# ControlBoard_p1.net
KiCad netlist of a schematic drawn in Altium Designer
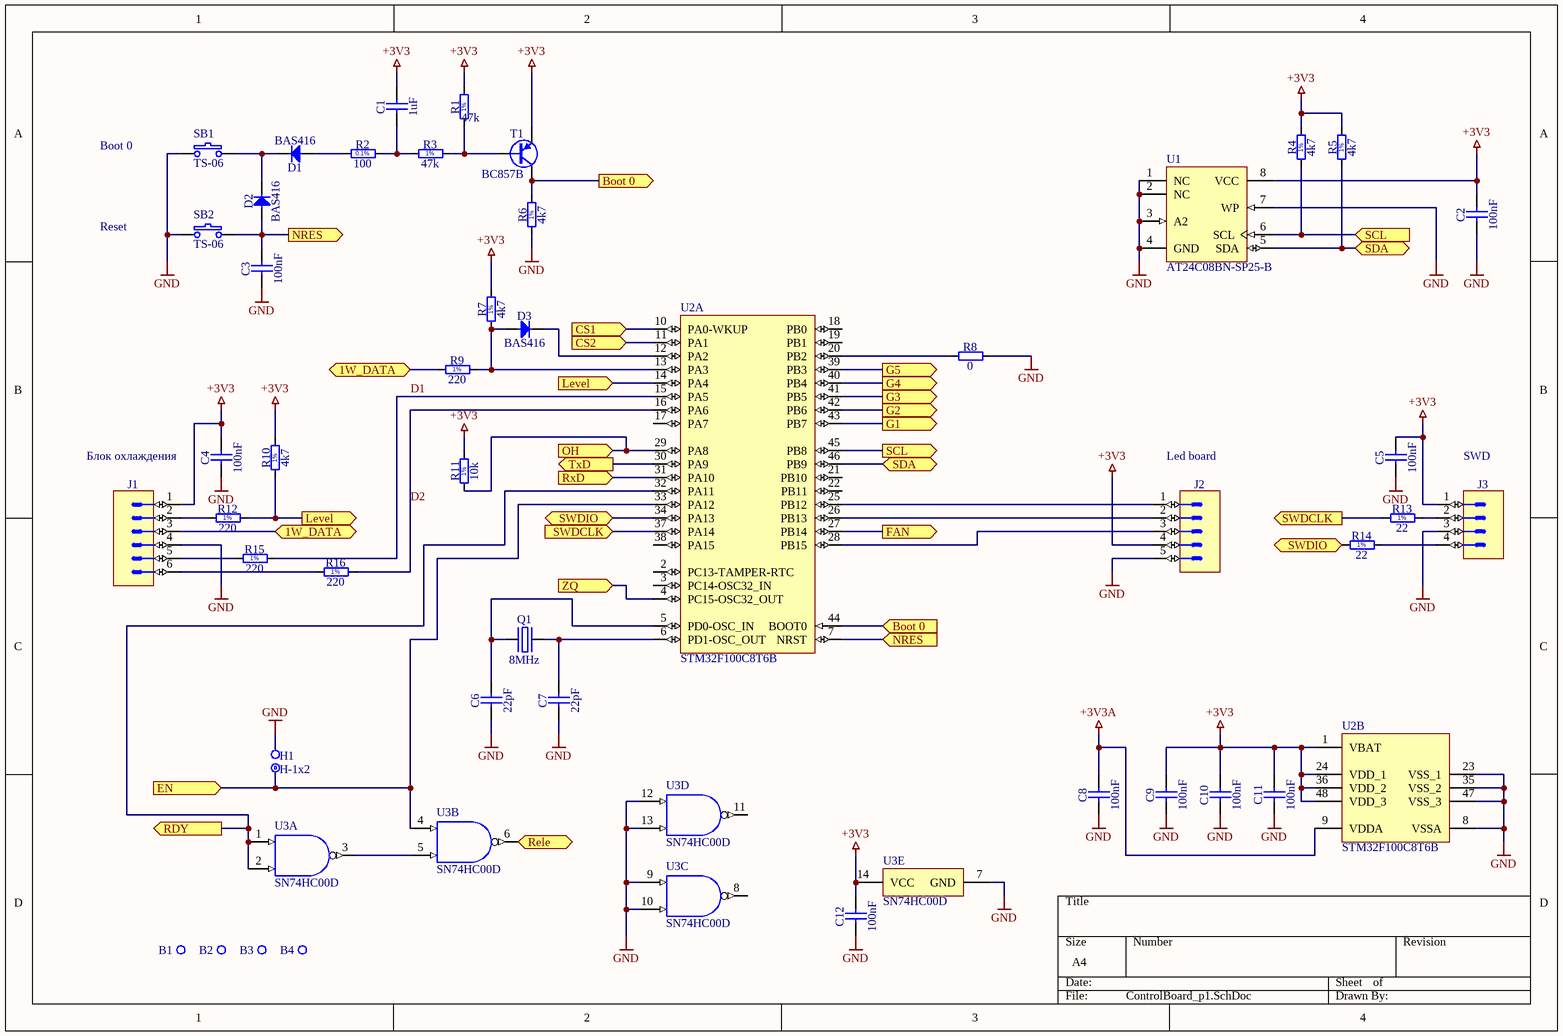
[diagram p0: ControlBoard_p1.SchDoc]

(export (version "E")
  (design (tool "Eeschema 10.0.6"))
  (components
    (comp (ref "B1")
      (value "Plated Hole")
      (footprint "MTG350_650")
      (description "Single Terminal Socket")
      (fields (field (name "PART NUMBER") "PLATED_HOLE3.5_PAD6.5") (field (name "AUTHOR") "CERN DEM JLC"))
      (libsource (lib "Eletro-mechanical") (part "Single Terminal Socket"))
    )
    (comp (ref "B2")
      (value "Plated Hole")
      (footprint "MTG350_650")
      (description "Single Terminal Socket")
      (fields (field (name "PART NUMBER") "PLATED_HOLE3.5_PAD6.5") (field (name "AUTHOR") "CERN DEM JLC"))
      (libsource (lib "Eletro-mechanical") (part "Single Terminal Socket"))
    )
    (comp (ref "B3")
      (value "Plated Hole")
      (footprint "MTG350_650")
      (description "Single Terminal Socket")
      (fields (field (name "PART NUMBER") "PLATED_HOLE3.5_PAD6.5") (field (name "AUTHOR") "CERN DEM JLC"))
      (libsource (lib "Eletro-mechanical") (part "Single Terminal Socket"))
    )
    (comp (ref "B4")
      (value "Plated Hole")
      (footprint "MTG350_650")
      (description "Single Terminal Socket")
      (fields (field (name "PART NUMBER") "PLATED_HOLE3.5_PAD6.5") (field (name "AUTHOR") "CERN DEM JLC"))
      (libsource (lib "Eletro-mechanical") (part "Single Terminal Socket"))
    )
    (comp (ref "C1")
      (value "1uF")
      (footprint "CAPC2012X140N")
      (description "Non-polarised capacitor")
      (fields
        (field (name "PART NUMBER") "CC0805_1UF_35V_20%_X7R")
        (field (name "VOLTAGE") "35V")
        (field (name "AUTHOR") "CERN DEM JLC")
      )
      (libsource (lib "Capacitors") (part "Capacitor - non polarized"))
    )
    (comp (ref "C2")
      (value "100nF")
      (footprint "CAPC2012X135N")
      (description "Non-polarised capacitor")
      (fields
        (field (name "PART NUMBER") "CC0805_100NF_50V_10%_X7R")
        (field (name "VOLTAGE") "50V")
        (field (name "AUTHOR") "CERN DEM JLC")
      )
      (libsource (lib "Capacitors") (part "Capacitor - non polarized"))
    )
    (comp (ref "C3")
      (value "100nF")
      (footprint "CAPC2012X135N")
      (description "Non-polarised capacitor")
      (fields
        (field (name "PART NUMBER") "CC0805_100NF_50V_10%_X7R")
        (field (name "VOLTAGE") "50V")
        (field (name "AUTHOR") "CERN DEM JLC")
      )
      (libsource (lib "Capacitors") (part "Capacitor - non polarized"))
    )
    (comp (ref "C4")
      (value "100nF")
      (footprint "CAPC2012X135N")
      (description "Non-polarised capacitor")
      (fields
        (field (name "PART NUMBER") "CC0805_100NF_50V_10%_X7R")
        (field (name "VOLTAGE") "50V")
        (field (name "AUTHOR") "CERN DEM JLC")
      )
      (libsource (lib "Capacitors") (part "Capacitor - non polarized"))
    )
    (comp (ref "C5")
      (value "100nF")
      (footprint "CAPC2012X135N")
      (description "Non-polarised capacitor")
      (fields
        (field (name "PART NUMBER") "CC0805_100NF_50V_10%_X7R")
        (field (name "VOLTAGE") "50V")
        (field (name "AUTHOR") "CERN DEM JLC")
      )
      (libsource (lib "Capacitors") (part "Capacitor - non polarized"))
    )
    (comp (ref "C6")
      (value "22pF")
      (footprint "CAPC2012X135N")
      (description "Non-polarised capacitor")
      (fields
        (field (name "PART NUMBER") "CC0805_22PF_50V_5%_NP0")
        (field (name "VOLTAGE") "50V")
        (field (name "AUTHOR") "CERN DEM JLC")
      )
      (libsource (lib "Capacitors") (part "Capacitor - non polarized"))
    )
    (comp (ref "C7")
      (value "22pF")
      (footprint "CAPC2012X135N")
      (description "Non-polarised capacitor")
      (fields
        (field (name "PART NUMBER") "CC0805_22PF_50V_5%_NP0")
        (field (name "VOLTAGE") "50V")
        (field (name "AUTHOR") "CERN DEM JLC")
      )
      (libsource (lib "Capacitors") (part "Capacitor - non polarized"))
    )
    (comp (ref "C8")
      (value "100nF")
      (footprint "CAPC2012X135N")
      (description "Non-polarised capacitor")
      (fields
        (field (name "PART NUMBER") "CC0805_100NF_50V_10%_X7R")
        (field (name "VOLTAGE") "50V")
        (field (name "AUTHOR") "CERN DEM JLC")
      )
      (libsource (lib "Capacitors") (part "Capacitor - non polarized"))
    )
    (comp (ref "C9")
      (value "100nF")
      (footprint "CAPC2012X135N")
      (description "Non-polarised capacitor")
      (fields
        (field (name "PART NUMBER") "CC0805_100NF_50V_10%_X7R")
        (field (name "VOLTAGE") "50V")
        (field (name "AUTHOR") "CERN DEM JLC")
      )
      (libsource (lib "Capacitors") (part "Capacitor - non polarized"))
    )
    (comp (ref "C10")
      (value "100nF")
      (footprint "CAPC2012X135N")
      (description "Non-polarised capacitor")
      (fields
        (field (name "PART NUMBER") "CC0805_100NF_50V_10%_X7R")
        (field (name "VOLTAGE") "50V")
        (field (name "AUTHOR") "CERN DEM JLC")
      )
      (libsource (lib "Capacitors") (part "Capacitor - non polarized"))
    )
    (comp (ref "C11")
      (value "100nF")
      (footprint "CAPC2012X135N")
      (description "Non-polarised capacitor")
      (fields
        (field (name "PART NUMBER") "CC0805_100NF_50V_10%_X7R")
        (field (name "VOLTAGE") "50V")
        (field (name "AUTHOR") "CERN DEM JLC")
      )
      (libsource (lib "Capacitors") (part "Capacitor - non polarized"))
    )
    (comp (ref "C12")
      (value "100nF")
      (footprint "CAPC2012X135N")
      (description "Non-polarised capacitor")
      (fields
        (field (name "PART NUMBER") "CC0805_100NF_50V_10%_X7R")
        (field (name "VOLTAGE") "50V")
        (field (name "AUTHOR") "CERN DEM JLC")
      )
      (libsource (lib "Capacitors") (part "Capacitor - non polarized"))
    )
    (comp (ref "D1")
      (value "BAS416")
      (footprint "SOD2512X110N")
      (description "Diode")
      (fields
        (field (name "VOLTAGE") "75V")
        (field (name "POWER") "200mA")
        (field (name "AUTHOR") "CERN DEM JLC")
      )
      (libsource (lib "ICs And Semiconductors") (part "Diode"))
    )
    (comp (ref "D2")
      (value "BAS416")
      (footprint "SOD2512X110N")
      (description "Diode")
      (fields
        (field (name "VOLTAGE") "75V")
        (field (name "POWER") "200mA")
        (field (name "AUTHOR") "CERN DEM JLC")
      )
      (libsource (lib "ICs And Semiconductors") (part "Diode"))
    )
    (comp (ref "D3")
      (value "BAS416")
      (footprint "SOD2512X110N")
      (description "Diode")
      (fields
        (field (name "VOLTAGE") "75V")
        (field (name "POWER") "200mA")
        (field (name "AUTHOR") "CERN DEM JLC")
      )
      (libsource (lib "ICs And Semiconductors") (part "Diode"))
    )
    (comp (ref "H1") (value "H-1x2") (footprint "J1x2") (libsource (lib "Connektor") (part "H-1x2")))
    (comp (ref "J1")
      (value "KK®")
      (footprint "MOLEX_22-27-2061")
      (description "Connector 6 Male")
      (fields
        (field (name "PART NUMBER") "MOLEX_22-27-2061")
        (field (name "MANUFACTURER") "MOLEX")
        (field (name "AUTHOR") "CERN DEM JMW")
      )
      (libsource (lib "Connectors") (part "Connector 6 Male"))
    )
    (comp (ref "J2")
      (value "KK®")
      (footprint "MOLEX_22-27-2051")
      (description "Connector 5 Male")
      (fields
        (field (name "PART NUMBER") "MOLEX_22-27-2051")
        (field (name "MANUFACTURER") "MOLEX")
        (field (name "AUTHOR") "CERN DEM JLC")
      )
      (libsource (lib "Connectors") (part "Connector 5 Male"))
    )
    (comp (ref "J3")
      (value "KK®")
      (footprint "MOLEX_22-27-2041")
      (description "Connector 4 Male")
      (fields
        (field (name "PART NUMBER") "MOLEX_22-27-2041")
        (field (name "MANUFACTURER") "MOLEX")
        (field (name "AUTHOR") "CERN DEM JLC")
      )
      (libsource (lib "Connectors") (part "Connector 4 Male"))
    )
    (comp (ref "Q1")
      (value "8MHz")
      (footprint "XTAL_HC-49/U-S")
      (description "Quartz Crystal")
      (fields
        (field (name "PART NUMBER") "XTAL_5MHZ_CITIZEN_HC49US5.000MABJ-UB")
        (field (name "MANUFACTURER") "CITIZEN FINETECH MIYOTA CO")
        (field (name "AUTHOR") "CERN DEM JLC")
      )
      (libsource (lib "ICs And Semiconductors") (part "Quartz Crystal"))
    )
    (comp (ref "R1")
      (value "47k")
      (footprint "RESC2012X60N")
      (description "Resistor - 1%")
      (fields
        (field (name "PART NUMBER") "R0805_47K_1%_0.125W_100PPM")
        (field (name "POWER") "0.125W")
        (field (name "AUTHOR") "CERN DEM JLC")
      )
      (libsource (lib "Resistors") (part "Resistor - 1%"))
    )
    (comp (ref "R2")
      (value "100")
      (footprint "RESC2012X60N")
      (description "Resistor - 0.1%")
      (fields
        (field (name "PART NUMBER") "R0805_100R_0.1%_0.1W_10PPM")
        (field (name "POWER") "0.1W")
        (field (name "AUTHOR") "CERN DEM JLC")
      )
      (libsource (lib "Resistors") (part "Resistor - 0.1%"))
    )
    (comp (ref "R3")
      (value "47k")
      (footprint "RESC2012X60N")
      (description "Resistor - 1%")
      (fields
        (field (name "PART NUMBER") "R0805_47K_1%_0.125W_100PPM")
        (field (name "POWER") "0.125W")
        (field (name "AUTHOR") "CERN DEM JLC")
      )
      (libsource (lib "Resistors") (part "Resistor - 1%"))
    )
    (comp (ref "R4")
      (value "4k7")
      (footprint "RESC2012X60N")
      (description "Resistor - 1%")
      (fields
        (field (name "PART NUMBER") "R0805_4K7_1%_0.125W_100PPM")
        (field (name "POWER") "0.125W")
        (field (name "AUTHOR") "CERN DEM JLC")
      )
      (libsource (lib "Resistors") (part "Resistor - 1%"))
    )
    (comp (ref "R5")
      (value "4k7")
      (footprint "RESC2012X60N")
      (description "Resistor - 1%")
      (fields
        (field (name "PART NUMBER") "R0805_4K7_1%_0.125W_100PPM")
        (field (name "POWER") "0.125W")
        (field (name "AUTHOR") "CERN DEM JLC")
      )
      (libsource (lib "Resistors") (part "Resistor - 1%"))
    )
    (comp (ref "R6")
      (value "4k7")
      (footprint "RESC2012X60N")
      (description "Resistor - 1%")
      (fields
        (field (name "PART NUMBER") "R0805_4K7_1%_0.125W_100PPM")
        (field (name "POWER") "0.125W")
        (field (name "AUTHOR") "CERN DEM JLC")
      )
      (libsource (lib "Resistors") (part "Resistor - 1%"))
    )
    (comp (ref "R7")
      (value "4k7")
      (footprint "RESC2012X60N")
      (description "Resistor - 1%")
      (fields
        (field (name "PART NUMBER") "R0805_4K7_1%_0.125W_100PPM")
        (field (name "POWER") "0.125W")
        (field (name "AUTHOR") "CERN DEM JLC")
      )
      (libsource (lib "Resistors") (part "Resistor - 1%"))
    )
    (comp (ref "R8")
      (value "0")
      (footprint "RESC2012X60N")
      (description "Resistor")
      (fields
        (field (name "PART NUMBER") "R0805_0R_JUMPER")
        (field (name "MANUFACTURER") "GENERIC")
        (field (name "AUTHOR") "CERN DEM JLC")
      )
      (libsource (lib "Resistors") (part "Resistor"))
    )
    (comp (ref "R9")
      (value "220")
      (footprint "RESC2012X60N")
      (description "Resistor - 1%")
      (fields
        (field (name "PART NUMBER") "R0805_220R_1%_0.125W_100PPM")
        (field (name "POWER") "0.125W")
        (field (name "AUTHOR") "CERN DEM JLC")
      )
      (libsource (lib "Resistors") (part "Resistor - 1%"))
    )
    (comp (ref "R10")
      (value "4k7")
      (footprint "RESC2012X60N")
      (description "Resistor - 1%")
      (fields
        (field (name "PART NUMBER") "R0805_4K7_1%_0.125W_100PPM")
        (field (name "POWER") "0.125W")
        (field (name "AUTHOR") "CERN DEM JLC")
      )
      (libsource (lib "Resistors") (part "Resistor - 1%"))
    )
    (comp (ref "R11")
      (value "10k")
      (footprint "RESC2012X60N")
      (description "Resistor - 1%")
      (fields
        (field (name "PART NUMBER") "R0805_10K_1%_0.125W_100PPM")
        (field (name "POWER") "0.125W")
        (field (name "AUTHOR") "CERN DEM JLC")
      )
      (libsource (lib "Resistors") (part "Resistor - 1%"))
    )
    (comp (ref "R12")
      (value "220")
      (footprint "RESC2012X60N")
      (description "Resistor - 1%")
      (fields
        (field (name "PART NUMBER") "R0805_220R_1%_0.125W_100PPM")
        (field (name "POWER") "0.125W")
        (field (name "AUTHOR") "CERN DEM JLC")
      )
      (libsource (lib "Resistors") (part "Resistor - 1%"))
    )
    (comp (ref "R13")
      (value "22")
      (footprint "RESC2012X60N")
      (description "Resistor - 1%")
      (fields
        (field (name "PART NUMBER") "R0805_22R_1%_0.125W_100PPM")
        (field (name "POWER") "0.125W")
        (field (name "AUTHOR") "CERN DEM JLC")
      )
      (libsource (lib "Resistors") (part "Resistor - 1%"))
    )
    (comp (ref "R14")
      (value "22")
      (footprint "RESC2012X60N")
      (description "Resistor - 1%")
      (fields
        (field (name "PART NUMBER") "R0805_22R_1%_0.125W_100PPM")
        (field (name "POWER") "0.125W")
        (field (name "AUTHOR") "CERN DEM JLC")
      )
      (libsource (lib "Resistors") (part "Resistor - 1%"))
    )
    (comp (ref "R15")
      (value "220")
      (footprint "RESC2012X60N")
      (description "Resistor - 1%")
      (fields
        (field (name "PART NUMBER") "R0805_220R_1%_0.125W_100PPM")
        (field (name "POWER") "0.125W")
        (field (name "AUTHOR") "CERN DEM JLC")
      )
      (libsource (lib "Resistors") (part "Resistor - 1%"))
    )
    (comp (ref "R16")
      (value "220")
      (footprint "RESC2012X60N")
      (description "Resistor - 1%")
      (fields
        (field (name "PART NUMBER") "R0805_220R_1%_0.125W_100PPM")
        (field (name "POWER") "0.125W")
        (field (name "AUTHOR") "CERN DEM JLC")
      )
      (libsource (lib "Resistors") (part "Resistor - 1%"))
    )
    (comp (ref "SB1") (value "TS-06") (footprint "TS-06") (libsource (lib "Devise") (part "Buton TS-06")))
    (comp (ref "SB2") (value "TS-06") (footprint "TS-06") (libsource (lib "Devise") (part "Buton TS-06")))
    (comp (ref "T1")
      (value "BC857B")
      (footprint "SOT95P230X110-3N")
      (description "PNP Transistor")
      (fields (field (name "MANUFACTURER") "NXP SEMICONDUCTORS") (field (name "AUTHOR") "CERN DEM JLC"))
      (libsource (lib "ICs And Semiconductors") (part "PNP B1 E2 C3"))
    )
    (comp (ref "U1")
      (value "AT24C08BN-SP25-B")
      (footprint "8S1_N")
      (description "8Kbit (1024 x 8), 2-wire Bus Automotive Serial EEPROM with Write Protect, 2.5V, 8-Pin SOIC, Bulk")
      (libsource (lib "Atmel Serial EEPROM") (part "AT24C08BN-SP25-B"))
    )
    (comp (ref "U2")
      (value "STM32F100C8T6B")
      (footprint "STM-LQFP48_N")
      (libsource (lib "STMicroelectronics STM32 F1") (part "STM32F100C8T6B"))
    )
    (comp (ref "U3")
      (value "SN74HC00D")
      (footprint "D0014A_N")
      (description "Quad 2-Input Positive-NAND Gates, D0014A, TUBE")
      (fields
        (field (name "GENERIC PART NUMBER") "SN74HC00")
        (field (name "MANUFACTURER") "Texas Instruments")
      )
      (libsource (lib "TI_Logic_Gate") (part "SN74HC00D"))
    )
  )
  (nets
    (net (code "1") (name "+3V3") (class "Default")
      (node (ref "C1") (pin "2") (pinfunction "2_2") (pintype "passive"))
      (node (ref "C10") (pin "2") (pinfunction "2_2") (pintype "passive"))
      (node (ref "C11") (pin "2") (pinfunction "2_2") (pintype "passive"))
      (node (ref "C12") (pin "2") (pinfunction "2_2") (pintype "passive"))
      (node (ref "C2") (pin "2") (pinfunction "2_2") (pintype "passive"))
      (node (ref "C4") (pin "2") (pinfunction "2_2") (pintype "passive"))
      (node (ref "C5") (pin "2") (pinfunction "2_2") (pintype "passive"))
      (node (ref "C9") (pin "2") (pinfunction "2_2") (pintype "passive"))
      (node (ref "J1") (pin "1") (pinfunction "1_1") (pintype "bidirectional"))
      (node (ref "J2") (pin "4") (pinfunction "4_4") (pintype "bidirectional"))
      (node (ref "J3") (pin "1") (pinfunction "1_1") (pintype "bidirectional"))
      (node (ref "R1") (pin "2") (pinfunction "2_2") (pintype "passive"))
      (node (ref "R10") (pin "2") (pinfunction "2_2") (pintype "passive"))
      (node (ref "R11") (pin "2") (pinfunction "2_2") (pintype "passive"))
      (node (ref "R4") (pin "2") (pinfunction "2_2") (pintype "passive"))
      (node (ref "R5") (pin "2") (pinfunction "2_2") (pintype "passive"))
      (node (ref "R7") (pin "2") (pinfunction "2_2") (pintype "passive"))
      (node (ref "T1") (pin "2") (pinfunction "E_2") (pintype "passive"))
      (node (ref "U1") (pin "8") (pinfunction "VCC_8") (pintype "power_in"))
      (node (ref "U2") (pin "1") (pinfunction "VBAT_1") (pintype "power_in"))
      (node (ref "U2") (pin "24") (pinfunction "VDD_1_24") (pintype "power_in"))
      (node (ref "U2") (pin "36") (pinfunction "VDD_2_36") (pintype "power_in"))
      (node (ref "U2") (pin "48") (pinfunction "VDD_3_48") (pintype "power_in"))
      (node (ref "U3") (pin "14") (pinfunction "VCC_14") (pintype "power_in"))
    )
    (net (code "2") (name "+3V3A") (class "Default")
      (node (ref "C8") (pin "2") (pinfunction "2_2") (pintype "passive"))
      (node (ref "U2") (pin "9") (pinfunction "VDDA_9") (pintype "power_in"))
    )
    (net (code "3") (name "/1W_DATA") (class "Default")
      (node (ref "J1") (pin "3") (pinfunction "3_3") (pintype "bidirectional"))
      (node (ref "R9") (pin "1") (pinfunction "1_1") (pintype "passive"))
    )
    (net (code "4") (name "/Boot 0") (class "Default")
      (node (ref "R6") (pin "2") (pinfunction "2_2") (pintype "passive"))
      (node (ref "T1") (pin "3") (pinfunction "C_3") (pintype "passive"))
      (node (ref "U2") (pin "44") (pinfunction "BOOT0_44") (pintype "input"))
    )
    (net (code "5") (name "/CS1") (class "Default")
      (node (ref "U2") (pin "10") (pinfunction "PA0-WKUP_10") (pintype "bidirectional"))
    )
    (net (code "6") (name "/CS2") (class "Default")
      (node (ref "U2") (pin "11") (pinfunction "PA1_11") (pintype "bidirectional"))
    )
    (net (code "7") (name "/D1") (class "Default")
      (node (ref "R15") (pin "2") (pinfunction "2_2") (pintype "passive"))
      (node (ref "U2") (pin "15") (pinfunction "PA5_15") (pintype "bidirectional"))
    )
    (net (code "8") (name "/D2") (class "Default")
      (node (ref "R16") (pin "2") (pinfunction "2_2") (pintype "passive"))
      (node (ref "U2") (pin "16") (pinfunction "PA6_16") (pintype "bidirectional"))
    )
    (net (code "9") (name "/EN") (class "Default")
      (node (ref "H1") (pin "1") (pinfunction "1_1") (pintype "passive"))
      (node (ref "U2") (pin "33") (pinfunction "PA12_33") (pintype "bidirectional"))
      (node (ref "U3") (pin "4") (pinfunction "2A_4") (pintype "input"))
    )
    (net (code "10") (name "/FAN") (class "Default")
      (node (ref "U2") (pin "27") (pinfunction "PB14_27") (pintype "bidirectional"))
    )
    (net (code "11") (name "/G1") (class "Default")
      (node (ref "U2") (pin "43") (pinfunction "PB7_43") (pintype "bidirectional"))
    )
    (net (code "12") (name "/G2") (class "Default")
      (node (ref "U2") (pin "42") (pinfunction "PB6_42") (pintype "bidirectional"))
    )
    (net (code "13") (name "/G3") (class "Default")
      (node (ref "U2") (pin "41") (pinfunction "PB5_41") (pintype "bidirectional"))
    )
    (net (code "14") (name "/G4") (class "Default")
      (node (ref "U2") (pin "40") (pinfunction "PB4_40") (pintype "bidirectional"))
    )
    (net (code "15") (name "/G5") (class "Default")
      (node (ref "U2") (pin "39") (pinfunction "PB3_39") (pintype "bidirectional"))
    )
    (net (code "16") (name "/Level") (class "Default")
      (node (ref "R10") (pin "1") (pinfunction "1_1") (pintype "passive"))
      (node (ref "R12") (pin "2") (pinfunction "2_2") (pintype "passive"))
      (node (ref "U2") (pin "14") (pinfunction "PA4_14") (pintype "bidirectional"))
    )
    (net (code "17") (name "/NRES") (class "Default")
      (node (ref "C3") (pin "2") (pinfunction "2_2") (pintype "passive"))
      (node (ref "D2") (pin "2") (pinfunction "A_2") (pintype "passive"))
      (node (ref "SB2") (pin "2") (pinfunction "2_2") (pintype "passive"))
      (node (ref "U2") (pin "7") (pinfunction "NRST_7") (pintype "bidirectional"))
    )
    (net (code "18") (name "/OH") (class "Default")
      (node (ref "R11") (pin "1") (pinfunction "1_1") (pintype "passive"))
      (node (ref "U2") (pin "29") (pinfunction "PA8_29") (pintype "bidirectional"))
    )
    (net (code "19") (name "/RDY") (class "Default")
      (node (ref "U2") (pin "32") (pinfunction "PA11_32") (pintype "bidirectional"))
      (node (ref "U3") (pin "1") (pinfunction "1A_1") (pintype "input"))
      (node (ref "U3") (pin "2") (pinfunction "1B_2") (pintype "input"))
    )
    (net (code "20") (name "/Rele") (class "Default")
      (node (ref "U3") (pin "6") (pinfunction "2Y_6") (pintype "output"))
    )
    (net (code "21") (name "/RxD") (class "Default")
      (node (ref "U2") (pin "31") (pinfunction "PA10_31") (pintype "bidirectional"))
    )
    (net (code "22") (name "/SCL") (class "Default")
      (node (ref "R4") (pin "1") (pinfunction "1_1") (pintype "passive"))
      (node (ref "U1") (pin "6") (pinfunction "SCL_6") (pintype "input"))
      (node (ref "U2") (pin "45") (pinfunction "PB8_45") (pintype "bidirectional"))
    )
    (net (code "23") (name "/SDA") (class "Default")
      (node (ref "R5") (pin "1") (pinfunction "1_1") (pintype "passive"))
      (node (ref "U1") (pin "5") (pinfunction "SDA_5") (pintype "bidirectional"))
      (node (ref "U2") (pin "46") (pinfunction "PB9_46") (pintype "bidirectional"))
    )
    (net (code "24") (name "/SWDCLK") (class "Default")
      (node (ref "R13") (pin "1") (pinfunction "1_1") (pintype "passive"))
      (node (ref "U2") (pin "37") (pinfunction "PA14_37") (pintype "bidirectional"))
    )
    (net (code "25") (name "/SWDIO") (class "Default")
      (node (ref "R14") (pin "1") (pinfunction "1_1") (pintype "passive"))
      (node (ref "U2") (pin "34") (pinfunction "PA13_34") (pintype "bidirectional"))
    )
    (net (code "26") (name "/TxD") (class "Default")
      (node (ref "U2") (pin "30") (pinfunction "PA9_30") (pintype "bidirectional"))
    )
    (net (code "27") (name "/ZQ") (class "Default")
      (node (ref "U2") (pin "4") (pinfunction "PC15-OSC32_OUT_4") (pintype "bidirectional"))
    )
    (net (code "28") (name "GND") (class "Default")
      (node (ref "C10") (pin "1") (pinfunction "1_1") (pintype "passive"))
      (node (ref "C11") (pin "1") (pinfunction "1_1") (pintype "passive"))
      (node (ref "C12") (pin "1") (pinfunction "1_1") (pintype "passive"))
      (node (ref "C2") (pin "1") (pinfunction "1_1") (pintype "passive"))
      (node (ref "C3") (pin "1") (pinfunction "1_1") (pintype "passive"))
      (node (ref "C4") (pin "1") (pinfunction "1_1") (pintype "passive"))
      (node (ref "C5") (pin "1") (pinfunction "1_1") (pintype "passive"))
      (node (ref "C6") (pin "1") (pinfunction "1_1") (pintype "passive"))
      (node (ref "C7") (pin "1") (pinfunction "1_1") (pintype "passive"))
      (node (ref "C8") (pin "1") (pinfunction "1_1") (pintype "passive"))
      (node (ref "C9") (pin "1") (pinfunction "1_1") (pintype "passive"))
      (node (ref "H1") (pin "2") (pinfunction "2_2") (pintype "passive"))
      (node (ref "J1") (pin "4") (pinfunction "4_4") (pintype "bidirectional"))
      (node (ref "J2") (pin "5") (pinfunction "5_5") (pintype "bidirectional"))
      (node (ref "J3") (pin "3") (pinfunction "3_3") (pintype "bidirectional"))
      (node (ref "R6") (pin "1") (pinfunction "1_1") (pintype "passive"))
      (node (ref "R8") (pin "2") (pinfunction "2_2") (pintype "passive"))
      (node (ref "SB1") (pin "1") (pinfunction "1_1") (pintype "passive"))
      (node (ref "SB2") (pin "1") (pinfunction "1_1") (pintype "passive"))
      (node (ref "U1") (pin "1") (pinfunction "NC_1") (pintype "passive"))
      (node (ref "U1") (pin "2") (pinfunction "NC_2") (pintype "passive"))
      (node (ref "U1") (pin "3") (pinfunction "A2_3") (pintype "input"))
      (node (ref "U1") (pin "4") (pinfunction "GND_4") (pintype "power_in"))
      (node (ref "U1") (pin "7") (pinfunction "WP_7") (pintype "input"))
      (node (ref "U2") (pin "23") (pinfunction "VSS_1_23") (pintype "power_in"))
      (node (ref "U2") (pin "35") (pinfunction "VSS_2_35") (pintype "power_in"))
      (node (ref "U2") (pin "47") (pinfunction "VSS_3_47") (pintype "power_in"))
      (node (ref "U2") (pin "8") (pinfunction "VSSA_8") (pintype "power_in"))
      (node (ref "U3") (pin "10") (pinfunction "3B_10") (pintype "input"))
      (node (ref "U3") (pin "12") (pinfunction "4A_12") (pintype "input"))
      (node (ref "U3") (pin "13") (pinfunction "4B_13") (pintype "input"))
      (node (ref "U3") (pin "7") (pinfunction "GND_7") (pintype "power_in"))
      (node (ref "U3") (pin "9") (pinfunction "3A_9") (pintype "input"))
    )
    (net (code "29") (name "Net-(C1-Pad1)") (class "Default")
      (node (ref "C1") (pin "1") (pinfunction "1_1") (pintype "passive"))
      (node (ref "R2") (pin "2") (pinfunction "2_2") (pintype "passive"))
      (node (ref "R3") (pin "1") (pinfunction "1_1") (pintype "passive"))
    )
    (net (code "30") (name "Net-(D1-A)") (class "Default")
      (node (ref "D1") (pin "2") (pinfunction "A_2") (pintype "passive"))
      (node (ref "R2") (pin "1") (pinfunction "1_1") (pintype "passive"))
    )
    (net (code "31") (name "Net-(D1-C)") (class "Default")
      (node (ref "D1") (pin "1") (pinfunction "C_1") (pintype "passive"))
      (node (ref "D2") (pin "1") (pinfunction "C_1") (pintype "passive"))
      (node (ref "SB1") (pin "2") (pinfunction "2_2") (pintype "passive"))
    )
    (net (code "32") (name "Net-(D3-A)") (class "Default")
      (node (ref "D3") (pin "2") (pinfunction "A_2") (pintype "passive"))
      (node (ref "R7") (pin "1") (pinfunction "1_1") (pintype "passive"))
      (node (ref "R9") (pin "2") (pinfunction "2_2") (pintype "passive"))
      (node (ref "U2") (pin "13") (pinfunction "PA3_13") (pintype "bidirectional"))
    )
    (net (code "33") (name "Net-(D3-C)") (class "Default")
      (node (ref "D3") (pin "1") (pinfunction "C_1") (pintype "passive"))
      (node (ref "U2") (pin "12") (pinfunction "PA2_12") (pintype "bidirectional"))
    )
    (net (code "34") (name "Net-(J1-Pad2)") (class "Default")
      (node (ref "J1") (pin "2") (pinfunction "2_2") (pintype "bidirectional"))
      (node (ref "R12") (pin "1") (pinfunction "1_1") (pintype "passive"))
    )
    (net (code "35") (name "Net-(J1-Pad5)") (class "Default")
      (node (ref "J1") (pin "5") (pinfunction "5_5") (pintype "bidirectional"))
      (node (ref "R15") (pin "1") (pinfunction "1_1") (pintype "passive"))
    )
    (net (code "36") (name "Net-(J1-Pad6)") (class "Default")
      (node (ref "J1") (pin "6") (pinfunction "6_6") (pintype "bidirectional"))
      (node (ref "R16") (pin "1") (pinfunction "1_1") (pintype "passive"))
    )
    (net (code "37") (name "Net-(J3-Pad2)") (class "Default")
      (node (ref "J3") (pin "2") (pinfunction "2_2") (pintype "bidirectional"))
      (node (ref "R13") (pin "2") (pinfunction "2_2") (pintype "passive"))
    )
    (net (code "38") (name "Net-(J3-Pad4)") (class "Default")
      (node (ref "J3") (pin "4") (pinfunction "4_4") (pintype "bidirectional"))
      (node (ref "R14") (pin "2") (pinfunction "2_2") (pintype "passive"))
    )
    (net (code "39") (name "Net-(Q1-OSC1)") (class "Default")
      (node (ref "C6") (pin "2") (pinfunction "2_2") (pintype "passive"))
      (node (ref "Q1") (pin "1") (pinfunction "OSC1_1") (pintype "passive"))
      (node (ref "U2") (pin "5") (pinfunction "PD0-OSC_IN_5") (pintype "bidirectional"))
    )
    (net (code "40") (name "Net-(Q1-OSC2)") (class "Default")
      (node (ref "C7") (pin "2") (pinfunction "2_2") (pintype "passive"))
      (node (ref "Q1") (pin "2") (pinfunction "OSC2_2") (pintype "passive"))
      (node (ref "U2") (pin "6") (pinfunction "PD1-OSC_OUT_6") (pintype "bidirectional"))
    )
    (net (code "41") (name "Net-(T1-B)") (class "Default")
      (node (ref "R1") (pin "1") (pinfunction "1_1") (pintype "passive"))
      (node (ref "R3") (pin "2") (pinfunction "2_2") (pintype "passive"))
      (node (ref "T1") (pin "1") (pinfunction "B_1") (pintype "passive"))
    )
    (net (code "42") (name "Net-(U2A-PB2)") (class "Default")
      (node (ref "R8") (pin "1") (pinfunction "1_1") (pintype "passive"))
      (node (ref "U2") (pin "20") (pinfunction "PB2_20") (pintype "bidirectional"))
    )
    (net (code "43") (name "Net-(U2A-PB12)") (class "Default")
      (node (ref "J2") (pin "1") (pinfunction "1_1") (pintype "bidirectional"))
      (node (ref "U2") (pin "25") (pinfunction "PB12_25") (pintype "bidirectional"))
    )
    (net (code "44") (name "Net-(U2A-PB13)") (class "Default")
      (node (ref "J2") (pin "2") (pinfunction "2_2") (pintype "bidirectional"))
      (node (ref "U2") (pin "26") (pinfunction "PB13_26") (pintype "bidirectional"))
    )
    (net (code "45") (name "Net-(U2A-PB15)") (class "Default")
      (node (ref "J2") (pin "3") (pinfunction "3_3") (pintype "bidirectional"))
      (node (ref "U2") (pin "28") (pinfunction "PB15_28") (pintype "bidirectional"))
    )
    (net (code "46") (name "Net-(U3A-1Y)") (class "Default")
      (node (ref "U3") (pin "3") (pinfunction "1Y_3") (pintype "output"))
      (node (ref "U3") (pin "5") (pinfunction "2B_5") (pintype "input"))
    )
    (net (code "47") (name "unconnected-(B1-Pad1)") (class "Default")
      (node (ref "B1") (pin "1") (pinfunction "1_1") (pintype "bidirectional"))
    )
    (net (code "48") (name "unconnected-(B2-Pad1)") (class "Default")
      (node (ref "B2") (pin "1") (pinfunction "1_1") (pintype "bidirectional"))
    )
    (net (code "49") (name "unconnected-(B3-Pad1)") (class "Default")
      (node (ref "B3") (pin "1") (pinfunction "1_1") (pintype "bidirectional"))
    )
    (net (code "50") (name "unconnected-(B4-Pad1)") (class "Default")
      (node (ref "B4") (pin "1") (pinfunction "1_1") (pintype "bidirectional"))
    )
    (net (code "51") (name "unconnected-(U2A-PA7-Pad17)") (class "Default")
      (node (ref "U2") (pin "17") (pinfunction "PA7_17") (pintype "bidirectional"))
    )
    (net (code "52") (name "unconnected-(U2A-PA15-Pad38)") (class "Default")
      (node (ref "U2") (pin "38") (pinfunction "PA15_38") (pintype "bidirectional"))
    )
    (net (code "53") (name "unconnected-(U2A-PB0-Pad18)") (class "Default")
      (node (ref "U2") (pin "18") (pinfunction "PB0_18") (pintype "bidirectional"))
    )
    (net (code "54") (name "unconnected-(U2A-PB1-Pad19)") (class "Default")
      (node (ref "U2") (pin "19") (pinfunction "PB1_19") (pintype "bidirectional"))
    )
    (net (code "55") (name "unconnected-(U2A-PB10-Pad21)") (class "Default")
      (node (ref "U2") (pin "21") (pinfunction "PB10_21") (pintype "bidirectional"))
    )
    (net (code "56") (name "unconnected-(U2A-PB11-Pad22)") (class "Default")
      (node (ref "U2") (pin "22") (pinfunction "PB11_22") (pintype "bidirectional"))
    )
    (net (code "57") (name "unconnected-(U2A-PC13-TAMPER-RTC-Pad2)") (class "Default")
      (node (ref "U2") (pin "2") (pinfunction "PC13-TAMPER-RTC_2") (pintype "bidirectional"))
    )
    (net (code "58") (name "unconnected-(U2A-PC14-OSC32_IN-Pad3)") (class "Default")
      (node (ref "U2") (pin "3") (pinfunction "PC14-OSC32_IN_3") (pintype "bidirectional"))
    )
    (net (code "59") (name "unconnected-(U3C-3Y-Pad8)") (class "Default")
      (node (ref "U3") (pin "8") (pinfunction "3Y_8") (pintype "output"))
    )
    (net (code "60") (name "unconnected-(U3D-4Y-Pad11)") (class "Default")
      (node (ref "U3") (pin "11") (pinfunction "4Y_11") (pintype "output"))
    )
  )
)
